# Shield_Audio.net
KiCad netlist of a schematic drawn in EAGLE
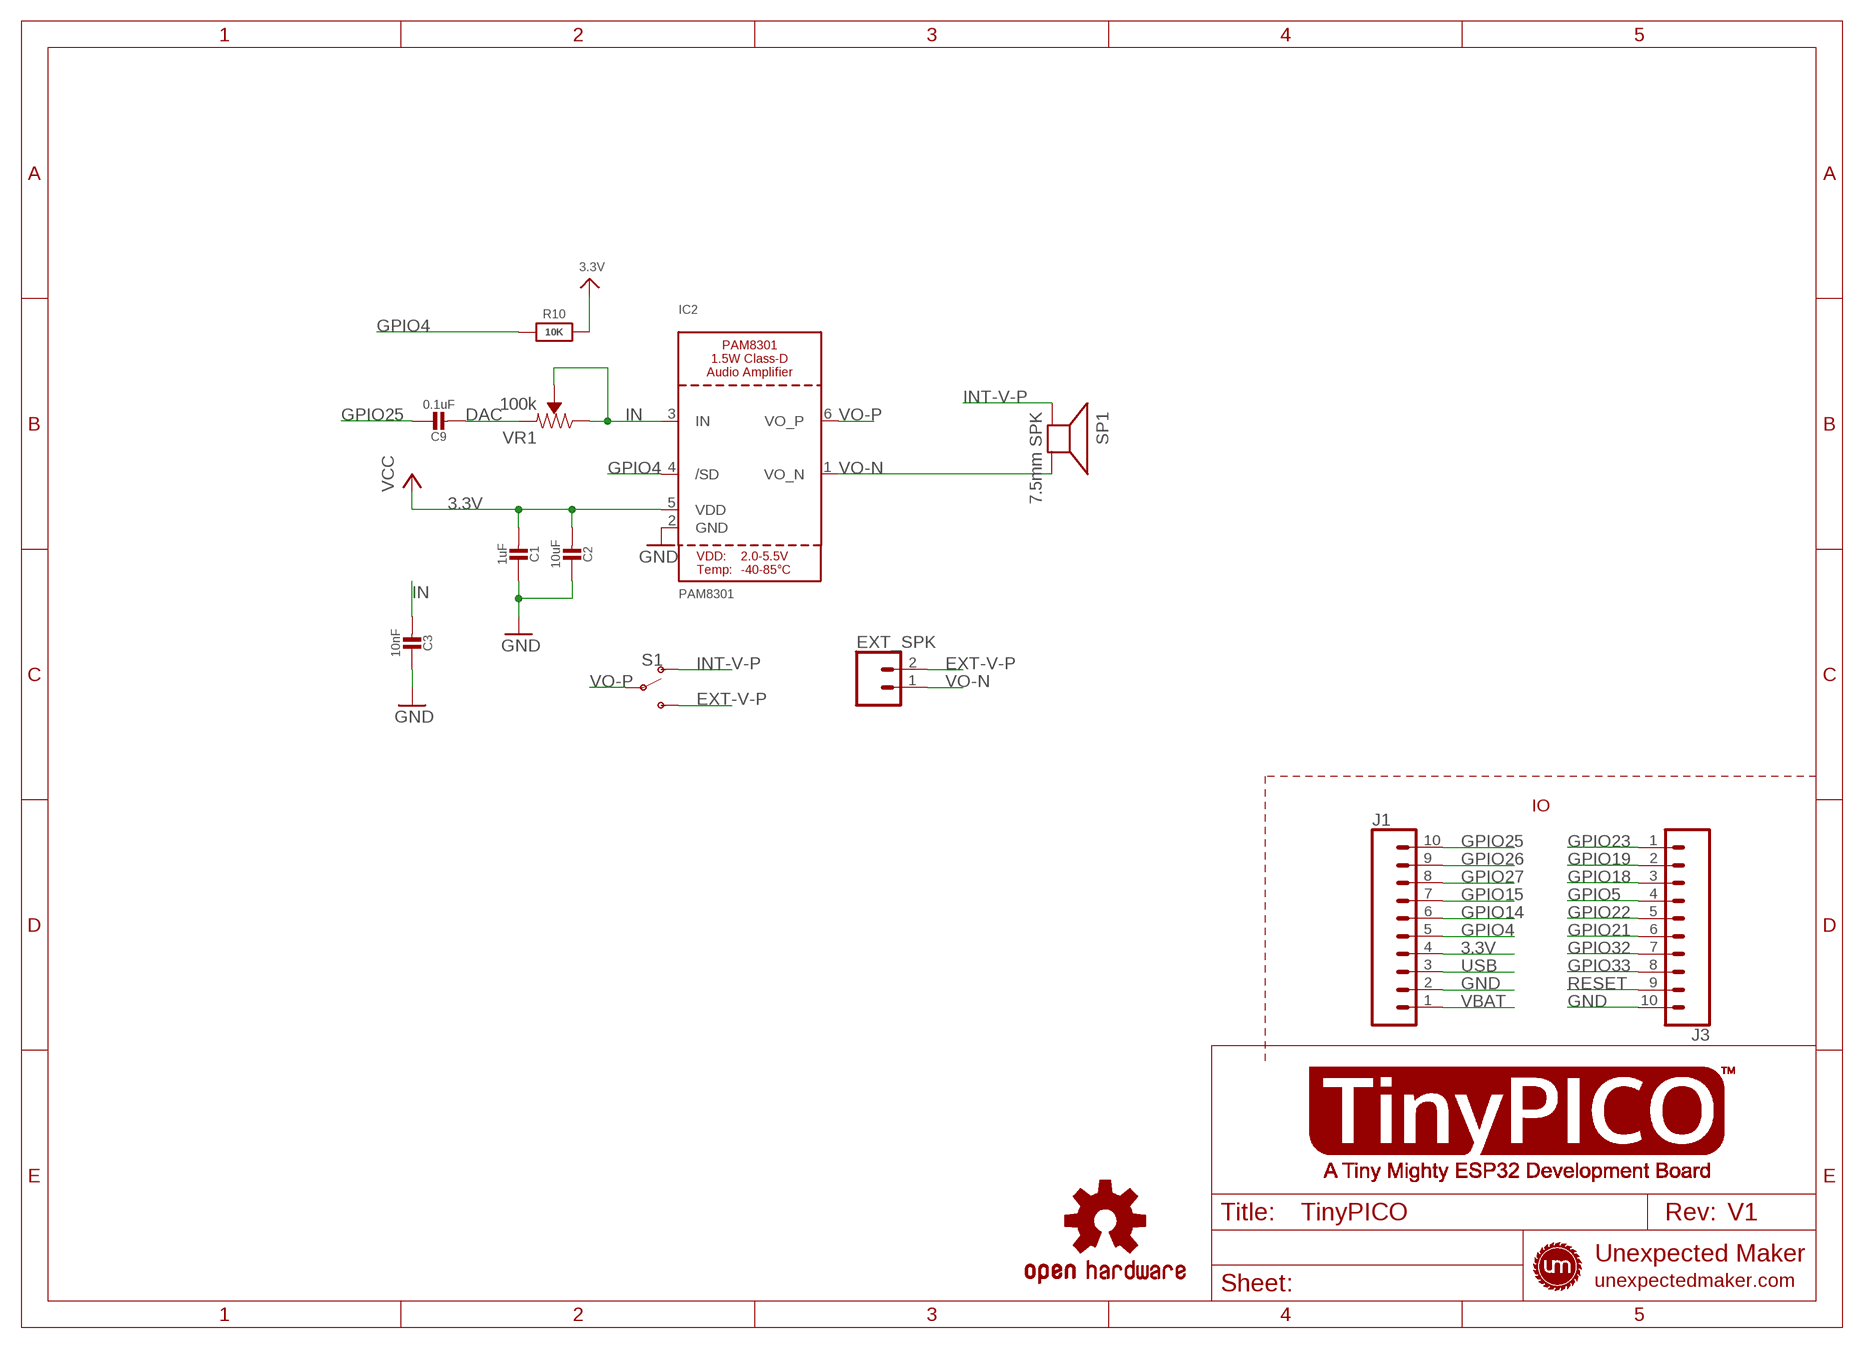
[diagram p0: schematic, sheet 1]

(export (version "E")
  (design (tool "Eeschema 10.0.6"))
  (components
    (comp (ref "C1")
      (value "1uF")
      (footprint "eagle-import:_0603MP")
      (libsource (lib "eagle-import") (part "CAP_CERAMIC_0603MP"))
    )
    (comp (ref "C2")
      (value "10uF")
      (footprint "eagle-import:_0603MP")
      (libsource (lib "eagle-import") (part "CAP_CERAMIC_0603MP"))
    )
    (comp (ref "C3")
      (value "10nF")
      (footprint "eagle-import:_0603MP")
      (libsource (lib "eagle-import") (part "CAP_CERAMIC_0603MP"))
    )
    (comp (ref "C9")
      (value "0.1uF")
      (footprint "eagle-import:_0603MP")
      (libsource (lib "eagle-import") (part "CAP_CERAMIC_0603MP"))
    )
    (comp (ref "EXT_SPK")
      (value "CONN_021X02_NO_SILK")
      (footprint "eagle-import:1X02_NO_SILK")
      (libsource (lib "eagle-import") (part "CONN_021X02_NO_SILK"))
    )
    (comp (ref "IC2")
      (value "PAM8301")
      (footprint "eagle-import:SOT23-6")
      (libsource (lib "eagle-import") (part "PAM8301"))
    )
    (comp (ref "J1")
      (value "TINYPICO_HEADER_10NO_SILK_PTH_FEMALE")
      (footprint "eagle-import:1X10_NO_SILK")
      (libsource (lib "eagle-import") (part "TINYPICO_HEADER_10NO_SILK_PTH_FEMALE"))
    )
    (comp (ref "J3")
      (value "TINYPICO_HEADER_10NO_SILK_PTH_FEMALE")
      (footprint "eagle-import:1X10_NO_SILK")
      (libsource (lib "eagle-import") (part "TINYPICO_HEADER_10NO_SILK_PTH_FEMALE"))
    )
    (comp (ref "LOGO1")
      (value "OSHW-LOGOS")
      (footprint "eagle-import:OSHW-LOGO-S")
      (libsource (lib "eagle-import") (part "OSHW-LOGOS"))
    )
    (comp (ref "R10")
      (value "10K")
      (footprint "eagle-import:_0603MP")
      (libsource (lib "eagle-import") (part "RESISTOR_0603MP"))
    )
    (comp (ref "S1")
      (value "SPARKFUN-SWITCHES_SWITCH-SPDT-SMD-RIGHT-ANGLE")
      (footprint "eagle-import:SPARKFUN-SWITCHES_SWITCH_SPST_SMD_A")
      (libsource (lib "eagle-import") (part "SPARKFUN-SWITCHES_SWITCH-SPDT-SMD-RIGHT-ANGLE"))
    )
    (comp (ref "SP1")
      (value "7.5mm SPK")
      (footprint "eagle-import:BUZZER_SMT_7.5MM")
      (libsource (lib "eagle-import") (part "SPEAKER_7.5MM"))
    )
    (comp (ref "VR1")
      (value "100k")
      (footprint "eagle-import:TRIMPOT-SMD-5MM")
      (libsource (lib "eagle-import") (part "TRIMPOT-SMD-5MM-CLOSED-1/4W-20%"))
    )
  )
  (nets
    (net (code "1") (name "/DAC") (class "Default")
      (node (ref "C9") (pin "2") (pinfunction "2_2") (pintype "passive"))
      (node (ref "VR1") (pin "A") (pinfunction "CCW_A") (pintype "passive"))
    )
    (net (code "2") (name "/EXT-V-P") (class "Default")
      (node (ref "EXT_SPK") (pin "2") (pinfunction "2_2") (pintype "passive"))
      (node (ref "S1") (pin "3") (pinfunction "S_3") (pintype "passive"))
    )
    (net (code "3") (name "/GPIO4") (class "Default")
      (node (ref "IC2") (pin "4") (pinfunction "/SD_4") (pintype "input"))
      (node (ref "J1") (pin "5") (pinfunction "5_5") (pintype "passive"))
      (node (ref "R10") (pin "1") (pinfunction "1_1") (pintype "passive"))
    )
    (net (code "4") (name "/GPIO5") (class "Default")
      (node (ref "J3") (pin "4") (pinfunction "4_4") (pintype "passive"))
    )
    (net (code "5") (name "/GPIO14") (class "Default")
      (node (ref "J1") (pin "6") (pinfunction "6_6") (pintype "passive"))
    )
    (net (code "6") (name "/GPIO15") (class "Default")
      (node (ref "J1") (pin "7") (pinfunction "7_7") (pintype "passive"))
    )
    (net (code "7") (name "/GPIO18") (class "Default")
      (node (ref "J3") (pin "3") (pinfunction "3_3") (pintype "passive"))
    )
    (net (code "8") (name "/GPIO19") (class "Default")
      (node (ref "J3") (pin "2") (pinfunction "2_2") (pintype "passive"))
    )
    (net (code "9") (name "/GPIO21") (class "Default")
      (node (ref "J3") (pin "6") (pinfunction "6_6") (pintype "passive"))
    )
    (net (code "10") (name "/GPIO22") (class "Default")
      (node (ref "J3") (pin "5") (pinfunction "5_5") (pintype "passive"))
    )
    (net (code "11") (name "/GPIO23") (class "Default")
      (node (ref "J3") (pin "1") (pinfunction "1_1") (pintype "passive"))
    )
    (net (code "12") (name "/GPIO25") (class "Default")
      (node (ref "C9") (pin "1") (pinfunction "1_1") (pintype "passive"))
      (node (ref "J1") (pin "10") (pinfunction "10_10") (pintype "passive"))
    )
    (net (code "13") (name "/GPIO26") (class "Default")
      (node (ref "J1") (pin "9") (pinfunction "9_9") (pintype "passive"))
    )
    (net (code "14") (name "/GPIO27") (class "Default")
      (node (ref "J1") (pin "8") (pinfunction "8_8") (pintype "passive"))
    )
    (net (code "15") (name "/GPIO32") (class "Default")
      (node (ref "J3") (pin "7") (pinfunction "7_7") (pintype "passive"))
    )
    (net (code "16") (name "/GPIO33") (class "Default")
      (node (ref "J3") (pin "8") (pinfunction "8_8") (pintype "passive"))
    )
    (net (code "17") (name "/IN") (class "Default")
      (node (ref "C3") (pin "2") (pinfunction "2_2") (pintype "passive"))
      (node (ref "IC2") (pin "3") (pinfunction "IN_3") (pintype "input"))
      (node (ref "VR1") (pin "B") (pinfunction "WIPER_B") (pintype "passive"))
      (node (ref "VR1") (pin "C") (pinfunction "CW_C") (pintype "passive"))
    )
    (net (code "18") (name "/INT-V-P") (class "Default")
      (node (ref "S1") (pin "1") (pinfunction "O_1") (pintype "passive"))
      (node (ref "SP1") (pin "+") (pinfunction "+_+") (pintype "passive"))
    )
    (net (code "19") (name "/RESET") (class "Default")
      (node (ref "J3") (pin "9") (pinfunction "9_9") (pintype "passive"))
    )
    (net (code "20") (name "/USB") (class "Default")
      (node (ref "J1") (pin "3") (pinfunction "3_3") (pintype "passive"))
    )
    (net (code "21") (name "/VBAT") (class "Default")
      (node (ref "J1") (pin "1") (pinfunction "1_1") (pintype "passive"))
    )
    (net (code "22") (name "/VO-N") (class "Default")
      (node (ref "EXT_SPK") (pin "1") (pinfunction "1_1") (pintype "passive"))
      (node (ref "IC2") (pin "1") (pinfunction "VO_N_1") (pintype "output"))
      (node (ref "SP1") (pin "-") (pinfunction "-_-") (pintype "passive"))
    )
    (net (code "23") (name "/VO-P") (class "Default")
      (node (ref "IC2") (pin "6") (pinfunction "VO_P_6") (pintype "output"))
      (node (ref "S1") (pin "2") (pinfunction "P_2") (pintype "passive"))
    )
    (net (code "24") (name "3.3V") (class "Default")
      (node (ref "C1") (pin "2") (pinfunction "2_2") (pintype "passive"))
      (node (ref "C2") (pin "2") (pinfunction "2_2") (pintype "passive"))
      (node (ref "IC2") (pin "5") (pinfunction "VDD_5") (pintype "power_in"))
      (node (ref "J1") (pin "4") (pinfunction "4_4") (pintype "passive"))
      (node (ref "R10") (pin "2") (pinfunction "2_2") (pintype "passive"))
    )
    (net (code "25") (name "GND") (class "Default")
      (node (ref "C1") (pin "1") (pinfunction "1_1") (pintype "passive"))
      (node (ref "C2") (pin "1") (pinfunction "1_1") (pintype "passive"))
      (node (ref "C3") (pin "1") (pinfunction "1_1") (pintype "passive"))
      (node (ref "IC2") (pin "2") (pinfunction "GND_2") (pintype "power_in"))
      (node (ref "J1") (pin "2") (pinfunction "2_2") (pintype "passive"))
      (node (ref "J3") (pin "10") (pinfunction "10_10") (pintype "passive"))
    )
  )
)
